# schematic_designe.net
KiCad netlist of a schematic drawn in EasyEDA
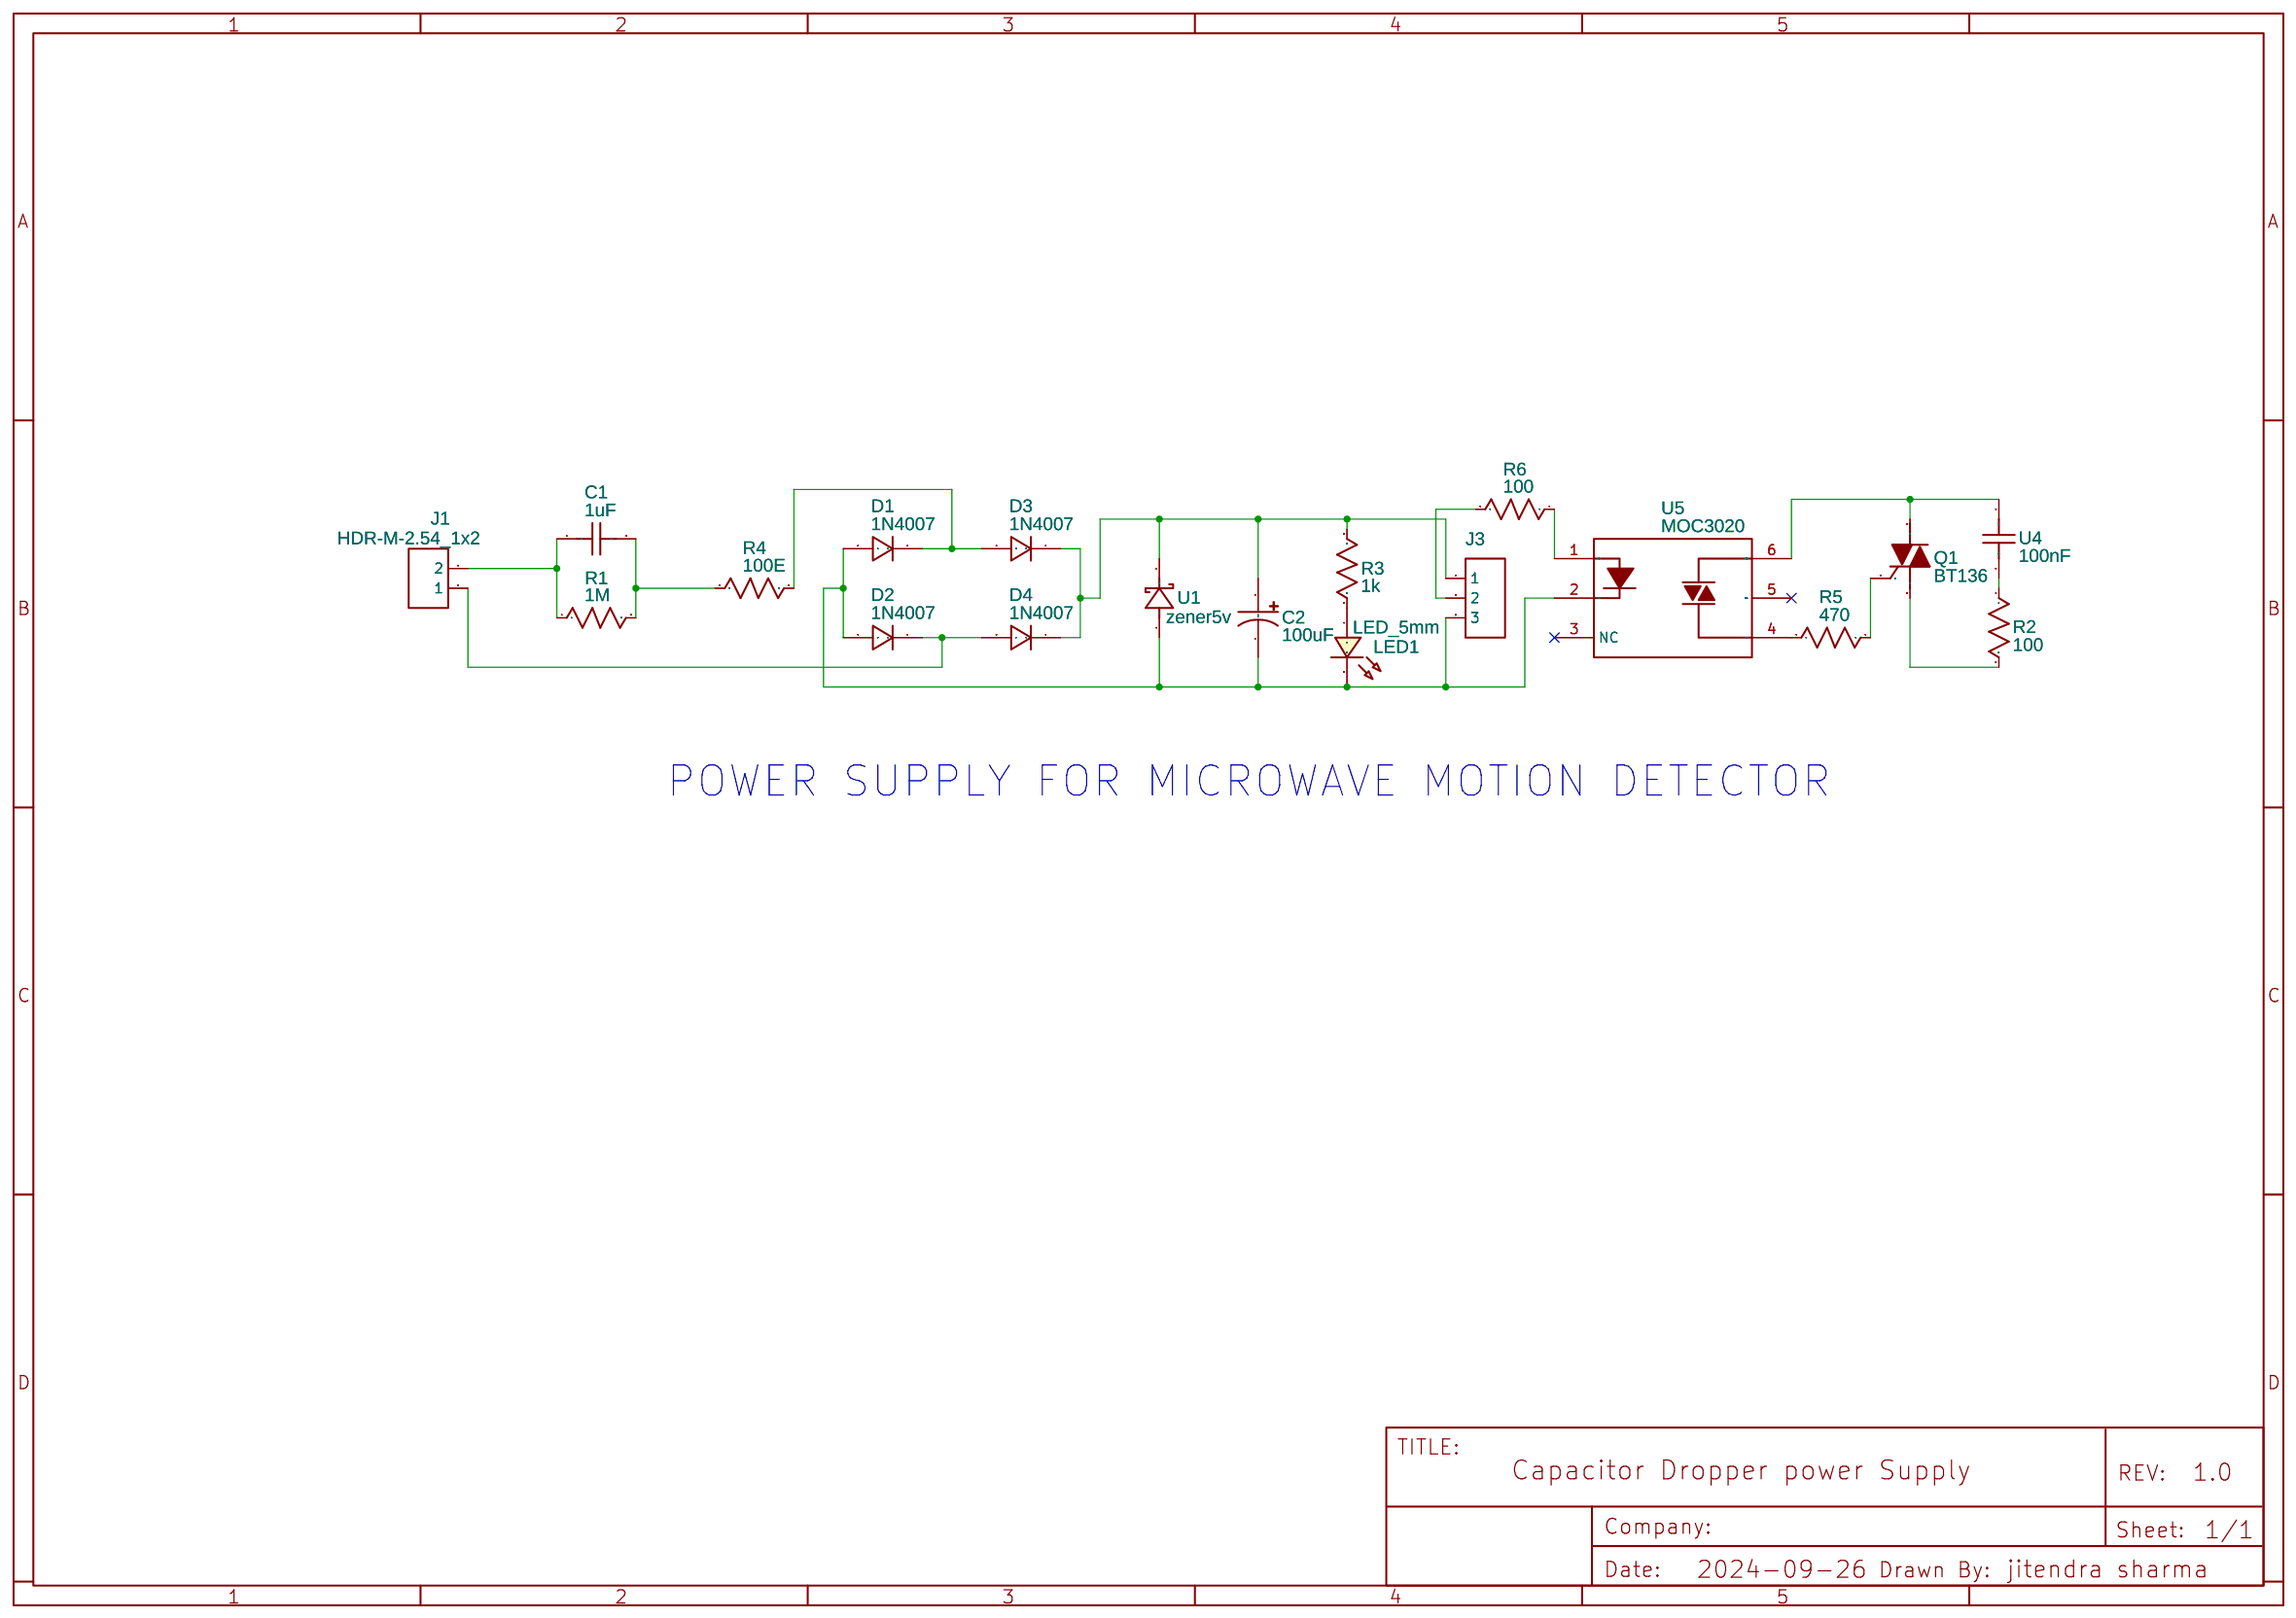
[diagram p0: schematic sheet]

(export (version "E")
  (design (tool "Eeschema 10.0.6"))
  (components
    (comp (ref "C1")
      (value "1uF")
      (fields (field (name "Manufacturer Part") "BFC237321105") (field (name "Manufacturer") "VISHAY(威世)"))
      (libsource (lib "") (part "BFC237321105"))
    )
    (comp (ref "C2")
      (value "100uF")
      (fields
        (field (name "Manufacturer Part") "KNE2100UF25V149EC0011")
        (field (name "Manufacturer") "KNSCHA(科尼盛)")
      )
      (libsource (lib "") (part "KNE2100UF25V149EC0011"))
    )
    (comp (ref "D1")
      (value "1N4007")
      (fields (field (name "Manufacturer") "SEMTECH"))
      (libsource (lib "") (part "1N4007"))
    )
    (comp (ref "D2")
      (value "1N4007")
      (fields (field (name "Manufacturer") "SEMTECH"))
      (libsource (lib "") (part "1N4007"))
    )
    (comp (ref "D3")
      (value "1N4007")
      (fields (field (name "Manufacturer") "SEMTECH"))
      (libsource (lib "") (part "1N4007"))
    )
    (comp (ref "D4")
      (value "1N4007")
      (fields (field (name "Manufacturer") "SEMTECH"))
      (libsource (lib "") (part "1N4007"))
    )
    (comp (ref "J1") (value "HDR-M-2.54_1x2") (libsource (lib "") (part "HDR-M-2.54_1x2")))
    (comp (ref "J3") (value "HDR-M-2.54_1x3") (libsource (lib "") (part "HDR-M-2.54_1x3")))
    (comp (ref "LED1")
      (value "LED_5mm")
      (fields
        (field (name "Manufacturer Part") "333-2SURD/S530-A3")
        (field (name "Manufacturer") "EVERLIGHT(台湾亿光)")
      )
      (libsource (lib "") (part "LED-TH-5mm_R"))
    )
    (comp (ref "Q1")
      (value "BT136")
      (fields (field (name "Manufacturer") "CJ(江苏长电/长晶)"))
      (libsource (lib "") (part "BT136"))
    )
    (comp (ref "R1") (value "1M") (libsource (lib "") (part "R_AXIAL-0.4_US_1")))
    (comp (ref "R2") (value "100") (libsource (lib "") (part "R_AXIAL-0.3_US")))
    (comp (ref "R3") (value "1k") (libsource (lib "") (part "R_AXIAL-0.4_US")))
    (comp (ref "R4") (value "100E") (libsource (lib "") (part "R_AXIAL-0.5_US")))
    (comp (ref "R5") (value "470") (libsource (lib "") (part "R_AXIAL-0.3_US_1")))
    (comp (ref "R6") (value "100") (libsource (lib "") (part "R_AXIAL-0.3_US_2")))
    (comp (ref "U1")
      (value "zener5v")
      (fields (field (name "Manufacturer Part") "1N4007-DIODE"))
      (libsource (lib "") (part "1N4007-DIODE"))
    )
    (comp (ref "U4")
      (value "100nF")
      (fields
        (field (name "Manufacturer Part") "MEB104J100V82CB0018")
        (field (name "Manufacturer") "KNSCHA(科尼盛)")
      )
      (libsource (lib "") (part "MEB104J100V82CB0018"))
    )
    (comp (ref "U5")
      (value "MOC3020")
      (fields (field (name "Manufacturer") "LITEON(光宝)"))
      (libsource (lib "") (part "MOC3020"))
    )
  )
  (nets
    (net (code "1") (name "Net-(C1-Pad1)") (class "Default")
      (node (ref "C1") (pin "1") (pinfunction "1_1") (pintype "unspecified"))
      (node (ref "J1") (pin "2") (pinfunction "2_2") (pintype "unspecified"))
      (node (ref "R1") (pin "1") (pinfunction "1_1") (pintype "unspecified"))
    )
    (net (code "2") (name "Net-(C1-Pad2)") (class "Default")
      (node (ref "C1") (pin "2") (pinfunction "2_2") (pintype "unspecified"))
      (node (ref "R1") (pin "2") (pinfunction "2_2") (pintype "unspecified"))
      (node (ref "R4") (pin "1") (pinfunction "1_1") (pintype "unspecified"))
    )
    (net (code "3") (name "Net-(D1-Pad1)") (class "Default")
      (node (ref "D1") (pin "1") (pinfunction "1_1") (pintype "unspecified"))
      (node (ref "D3") (pin "2") (pinfunction "2_2") (pintype "unspecified"))
      (node (ref "R4") (pin "2") (pinfunction "2_2") (pintype "unspecified"))
    )
    (net (code "4") (name "Net-(D2-Pad1)") (class "Default")
      (node (ref "D2") (pin "1") (pinfunction "1_1") (pintype "unspecified"))
      (node (ref "D4") (pin "2") (pinfunction "2_2") (pintype "unspecified"))
      (node (ref "J1") (pin "1") (pinfunction "1_1") (pintype "unspecified"))
    )
    (net (code "5") (name "Net-(J3-Pad2)") (class "Default")
      (node (ref "J3") (pin "2") (pinfunction "2_2") (pintype "input"))
      (node (ref "R6") (pin "2") (pinfunction "2_2") (pintype "unspecified"))
    )
    (net (code "6") (name "Net-(LED1-Pad1)") (class "Default")
      (node (ref "LED1") (pin "1") (pinfunction "1_1") (pintype "unspecified"))
      (node (ref "R3") (pin "2") (pinfunction "2_2") (pintype "unspecified"))
    )
    (net (code "7") (name "Net-(Q1-G)") (class "Default")
      (node (ref "Q1") (pin "3") (pinfunction "G_3") (pintype "unspecified"))
      (node (ref "R5") (pin "2") (pinfunction "2_2") (pintype "unspecified"))
    )
    (net (code "8") (name "Net-(Q1-M1)") (class "Default")
      (node (ref "Q1") (pin "1") (pinfunction "M1_1") (pintype "unspecified"))
      (node (ref "R2") (pin "2") (pinfunction "2_2") (pintype "unspecified"))
    )
    (net (code "9") (name "Net-(Q1-M2)") (class "Default")
      (node (ref "Q1") (pin "2") (pinfunction "M2_2") (pintype "unspecified"))
      (node (ref "U4") (pin "1") (pinfunction "1_1") (pintype "unspecified"))
      (node (ref "U5") (pin "6") (pinfunction "Terminal__6") (pintype "unspecified"))
    )
    (net (code "10") (name "Net-(R2-Pad1)") (class "Default")
      (node (ref "R2") (pin "1") (pinfunction "1_1") (pintype "unspecified"))
      (node (ref "U4") (pin "2") (pinfunction "2_2") (pintype "unspecified"))
    )
    (net (code "11") (name "Net-(U1-A)") (class "Default")
      (node (ref "C2") (pin "2") (pinfunction "2_2") (pintype "unspecified"))
      (node (ref "D1") (pin "2") (pinfunction "2_2") (pintype "unspecified"))
      (node (ref "D2") (pin "2") (pinfunction "2_2") (pintype "unspecified"))
      (node (ref "J3") (pin "3") (pinfunction "3_3") (pintype "input"))
      (node (ref "LED1") (pin "2") (pinfunction "2_2") (pintype "unspecified"))
      (node (ref "U1") (pin "1") (pinfunction "A_1") (pintype "unspecified"))
      (node (ref "U5") (pin "2") (pinfunction "Cathode__2") (pintype "unspecified"))
    )
    (net (code "12") (name "Net-(U1-K)") (class "Default")
      (node (ref "C2") (pin "1") (pinfunction "1_1") (pintype "unspecified"))
      (node (ref "D3") (pin "1") (pinfunction "1_1") (pintype "unspecified"))
      (node (ref "D4") (pin "1") (pinfunction "1_1") (pintype "unspecified"))
      (node (ref "J3") (pin "1") (pinfunction "1_1") (pintype "input"))
      (node (ref "R3") (pin "1") (pinfunction "1_1") (pintype "unspecified"))
      (node (ref "U1") (pin "2") (pinfunction "K_2") (pintype "unspecified"))
    )
    (net (code "13") (name "Net-(U5-ANODE)") (class "Default")
      (node (ref "R6") (pin "1") (pinfunction "1_1") (pintype "unspecified"))
      (node (ref "U5") (pin "1") (pinfunction "ANODE_1") (pintype "unspecified"))
    )
    (net (code "14") (name "Net-(U5-_Terminal)") (class "Default")
      (node (ref "R5") (pin "1") (pinfunction "1_1") (pintype "unspecified"))
      (node (ref "U5") (pin "4") (pinfunction "_Terminal_4") (pintype "unspecified"))
    )
    (net (code "15") (name "unconnected-(U5-NC-Pad3)") (class "Default")
      (node (ref "U5") (pin "3") (pinfunction "NC_3") (pintype "unspecified+no_connect"))
    )
    (net (code "16") (name "unconnected-(U5-Substrate_-Pad5)") (class "Default")
      (node (ref "U5") (pin "5") (pinfunction "Substrate__5") (pintype "unspecified+no_connect"))
    )
  )
)
